# SparkFun_9DoF_Sensor_Stick.net
KiCad netlist of a schematic drawn in EAGLE
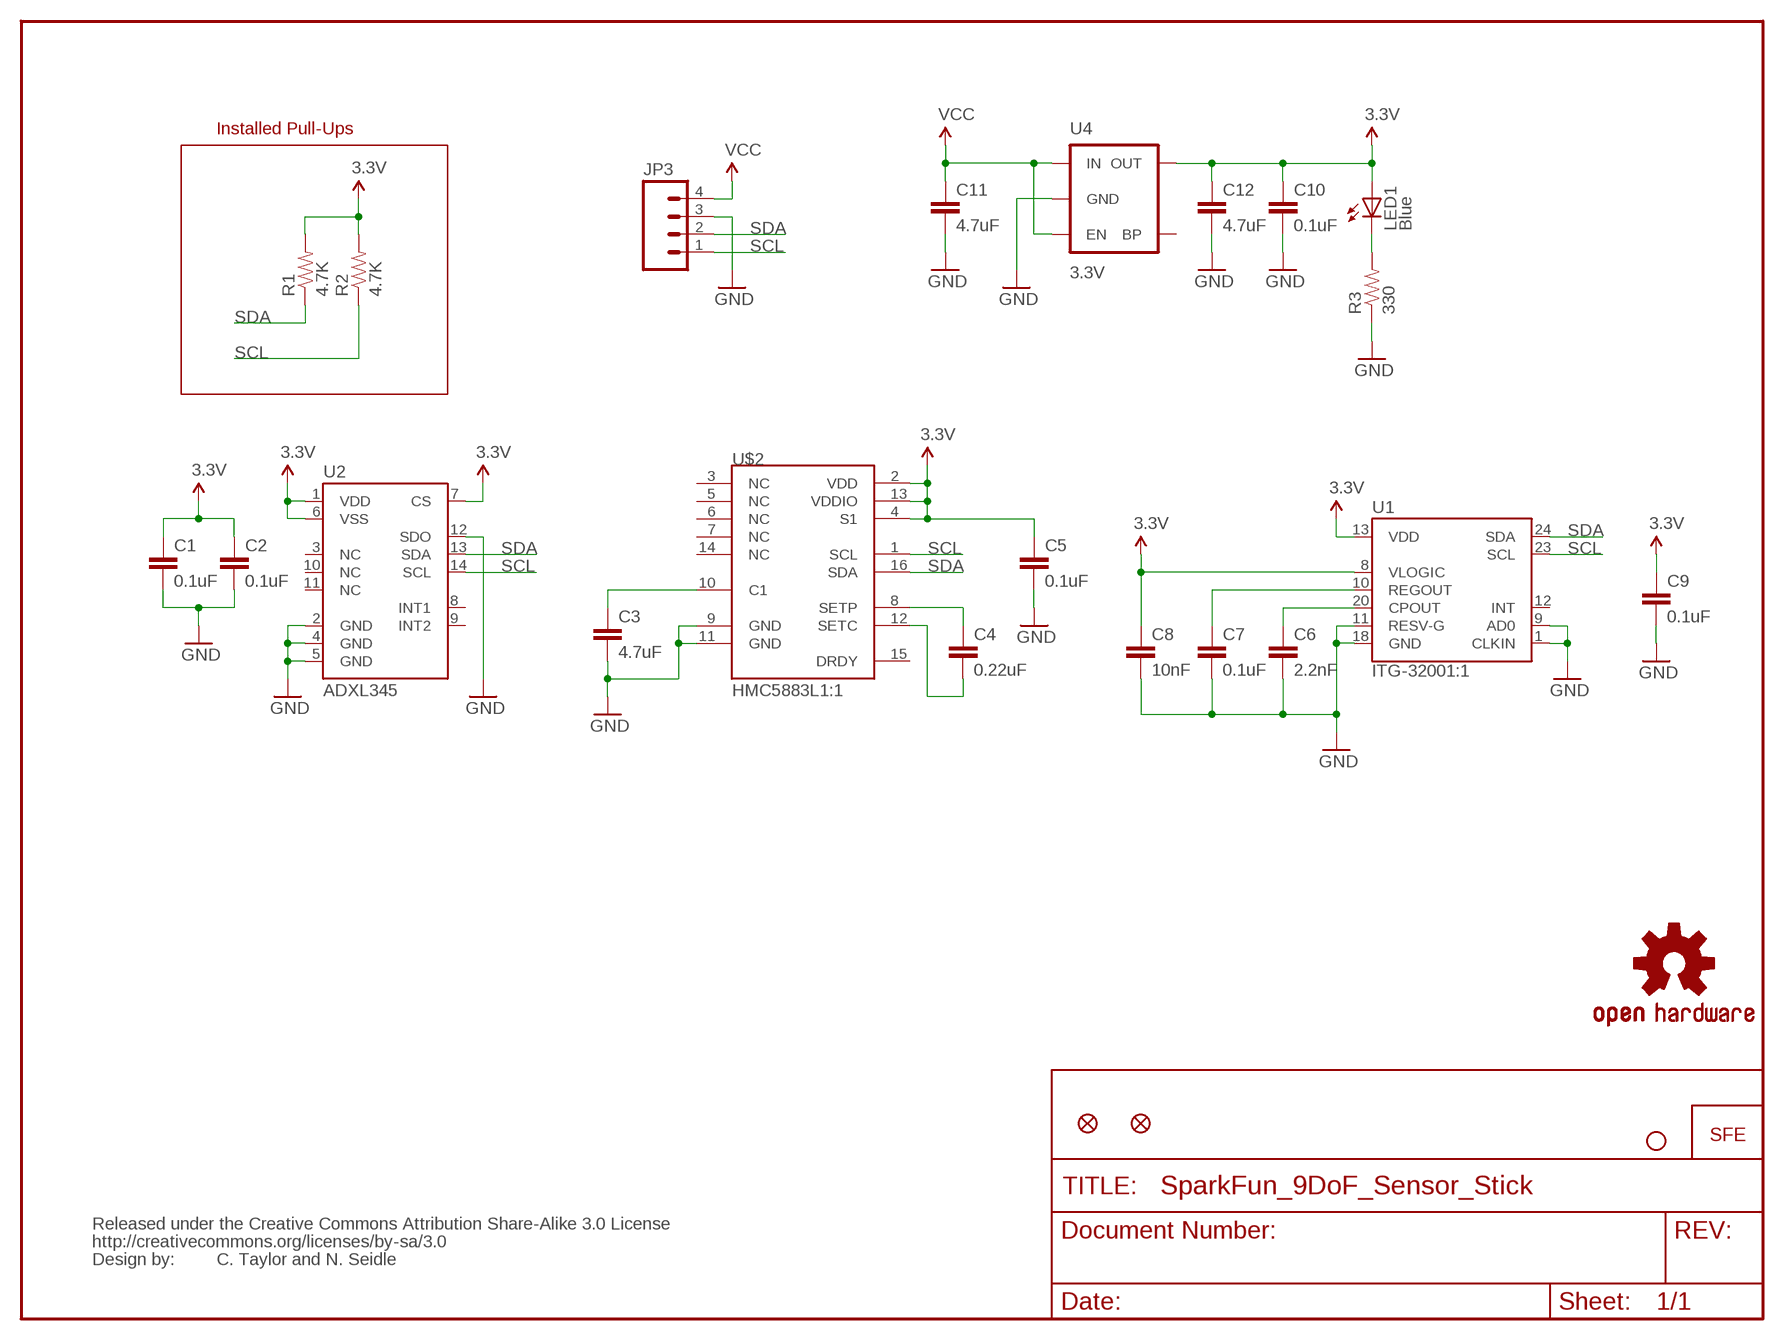
[diagram p0: schematic, sheet 1]

(export (version "E")
  (design (tool "Eeschema 10.0.6"))
  (components
    (comp (ref "C1")
      (value "0.1uF")
      (footprint "eagle-import:0402-CAP")
      (libsource (lib "eagle-import") (part "CAP0402-CAP"))
    )
    (comp (ref "C2")
      (value "0.1uF")
      (footprint "eagle-import:0402-CAP")
      (libsource (lib "eagle-import") (part "CAP0402-CAP"))
    )
    (comp (ref "C3")
      (value "4.7uF")
      (footprint "eagle-import:0402-CAP")
      (libsource (lib "eagle-import") (part "CAP0402-CAP"))
    )
    (comp (ref "C4")
      (value "0.22uF")
      (footprint "eagle-import:0402-CAP")
      (libsource (lib "eagle-import") (part "CAP0402-CAP"))
    )
    (comp (ref "C5")
      (value "0.1uF")
      (footprint "eagle-import:0402-CAP")
      (libsource (lib "eagle-import") (part "CAP0402-CAP"))
    )
    (comp (ref "C6")
      (value "2.2nF")
      (footprint "eagle-import:0402-CAP")
      (libsource (lib "eagle-import") (part "CAP0402-CAP"))
    )
    (comp (ref "C7")
      (value "0.1uF")
      (footprint "eagle-import:0402-CAP")
      (libsource (lib "eagle-import") (part "CAP0402-CAP"))
    )
    (comp (ref "C8")
      (value "10nF")
      (footprint "eagle-import:0402-CAP")
      (libsource (lib "eagle-import") (part "CAP0402-CAP"))
    )
    (comp (ref "C9")
      (value "0.1uF")
      (footprint "eagle-import:0402-CAP")
      (libsource (lib "eagle-import") (part "CAP0402-CAP"))
    )
    (comp (ref "C10")
      (value "0.1uF")
      (footprint "eagle-import:0402-CAP")
      (libsource (lib "eagle-import") (part "CAP0402-CAP"))
    )
    (comp (ref "C11")
      (value "4.7uF")
      (footprint "eagle-import:0402-CAP")
      (libsource (lib "eagle-import") (part "CAP0402-CAP"))
    )
    (comp (ref "C12")
      (value "4.7uF")
      (footprint "eagle-import:0402-CAP")
      (libsource (lib "eagle-import") (part "CAP0402-CAP"))
    )
    (comp (ref "JP1")
      (value "FIDUCIAL1X2")
      (footprint "eagle-import:FIDUCIAL-1X2")
      (libsource (lib "eagle-import") (part "FIDUCIAL1X2"))
    )
    (comp (ref "JP2")
      (value "FIDUCIAL1X2")
      (footprint "eagle-import:FIDUCIAL-1X2")
      (libsource (lib "eagle-import") (part "FIDUCIAL1X2"))
    )
    (comp (ref "JP3")
      (value "M04PTH")
      (footprint "eagle-import:1X04")
      (libsource (lib "eagle-import") (part "M04PTH"))
    )
    (comp (ref "JP4")
      (value "LOGO-SFESK")
      (footprint "eagle-import:SFE-LOGO-FLAME")
      (libsource (lib "eagle-import") (part "LOGO-SFESK"))
    )
    (comp (ref "JP5")
      (value "STAND-OFF")
      (footprint "eagle-import:STAND-OFF")
      (libsource (lib "eagle-import") (part "STAND-OFF"))
    )
    (comp (ref "LED1")
      (value "Blue")
      (footprint "eagle-import:LED-0603")
      (libsource (lib "eagle-import") (part "LED0603"))
    )
    (comp (ref "R1")
      (value "4.7K")
      (footprint "eagle-import:0402-RES")
      (libsource (lib "eagle-import") (part "RESISTOR0402-RES"))
    )
    (comp (ref "R2")
      (value "4.7K")
      (footprint "eagle-import:0402-RES")
      (libsource (lib "eagle-import") (part "RESISTOR0402-RES"))
    )
    (comp (ref "R3")
      (value "330")
      (footprint "eagle-import:0402-RES")
      (libsource (lib "eagle-import") (part "RESISTOR0402-RES"))
    )
    (comp (ref "U$1")
      (value "CREATIVE_COMMONS")
      (footprint "eagle-import:CREATIVE_COMMONS")
      (libsource (lib "eagle-import") (part "CREATIVE_COMMONS"))
    )
    (comp (ref "U$2")
      (value "HMC5883L1:1")
      (footprint "eagle-import:16LPCC_1_1")
      (libsource (lib "eagle-import") (part "HMC5883L1{colon}1"))
    )
    (comp (ref "U$3")
      (value "OSHW-LOGOS")
      (footprint "eagle-import:OSHW-LOGO-S")
      (libsource (lib "eagle-import") (part "OSHW-LOGOS"))
    )
    (comp (ref "U1")
      (value "ITG-32001:1")
      (footprint "eagle-import:QFN-24_1_1")
      (libsource (lib "eagle-import") (part "ITG-32001{colon}1"))
    )
    (comp (ref "U2")
      (value "ADXL345")
      (footprint "eagle-import:LGA14")
      (libsource (lib "eagle-import") (part "ADXL345"))
    )
    (comp (ref "U4")
      (value "3.3V")
      (footprint "eagle-import:SOT23-5")
      (libsource (lib "eagle-import") (part "V_REG_LDOSMD"))
    )
  )
  (nets
    (net (code "1") (name "/SCL") (class "Default")
      (node (ref "JP3") (pin "1") (pinfunction "1_1") (pintype "passive"))
      (node (ref "R2") (pin "1") (pinfunction "1_1") (pintype "passive"))
      (node (ref "U$2") (pin "1") (pinfunction "SCL_1") (pintype "bidirectional"))
      (node (ref "U1") (pin "23") (pinfunction "SCL_23") (pintype "bidirectional"))
      (node (ref "U2") (pin "14") (pinfunction "SCL_14") (pintype "bidirectional"))
    )
    (net (code "2") (name "/SDA") (class "Default")
      (node (ref "JP3") (pin "2") (pinfunction "2_2") (pintype "passive"))
      (node (ref "R1") (pin "1") (pinfunction "1_1") (pintype "passive"))
      (node (ref "U$2") (pin "16") (pinfunction "SDA_16") (pintype "bidirectional"))
      (node (ref "U1") (pin "24") (pinfunction "SDA_24") (pintype "bidirectional"))
      (node (ref "U2") (pin "13") (pinfunction "SDA_13") (pintype "bidirectional"))
    )
    (net (code "3") (name "3.3V") (class "Default")
      (node (ref "C1") (pin "1") (pinfunction "1_1") (pintype "passive"))
      (node (ref "C10") (pin "1") (pinfunction "1_1") (pintype "passive"))
      (node (ref "C12") (pin "1") (pinfunction "1_1") (pintype "passive"))
      (node (ref "C2") (pin "1") (pinfunction "1_1") (pintype "passive"))
      (node (ref "C5") (pin "1") (pinfunction "1_1") (pintype "passive"))
      (node (ref "C8") (pin "1") (pinfunction "1_1") (pintype "passive"))
      (node (ref "C9") (pin "1") (pinfunction "1_1") (pintype "passive"))
      (node (ref "LED1") (pin "A") (pinfunction "A_A") (pintype "passive"))
      (node (ref "R1") (pin "2") (pinfunction "2_2") (pintype "passive"))
      (node (ref "R2") (pin "2") (pinfunction "2_2") (pintype "passive"))
      (node (ref "U$2") (pin "13") (pinfunction "VDDIO_13") (pintype "bidirectional"))
      (node (ref "U$2") (pin "2") (pinfunction "VDD_2") (pintype "bidirectional"))
      (node (ref "U$2") (pin "4") (pinfunction "S1_4") (pintype "bidirectional"))
      (node (ref "U1") (pin "13") (pinfunction "VDD_13") (pintype "bidirectional"))
      (node (ref "U1") (pin "8") (pinfunction "VLOGIC_8") (pintype "bidirectional"))
      (node (ref "U2") (pin "1") (pinfunction "VDD_1") (pintype "bidirectional"))
      (node (ref "U2") (pin "6") (pinfunction "VSS_6") (pintype "bidirectional"))
      (node (ref "U2") (pin "7") (pinfunction "CS_7") (pintype "bidirectional"))
      (node (ref "U4") (pin "5") (pinfunction "OUT_5") (pintype "passive"))
    )
    (net (code "4") (name "GND") (class "Default")
      (node (ref "C1") (pin "2") (pinfunction "2_2") (pintype "passive"))
      (node (ref "C10") (pin "2") (pinfunction "2_2") (pintype "passive"))
      (node (ref "C11") (pin "2") (pinfunction "2_2") (pintype "passive"))
      (node (ref "C12") (pin "2") (pinfunction "2_2") (pintype "passive"))
      (node (ref "C2") (pin "2") (pinfunction "2_2") (pintype "passive"))
      (node (ref "C3") (pin "2") (pinfunction "2_2") (pintype "passive"))
      (node (ref "C5") (pin "2") (pinfunction "2_2") (pintype "passive"))
      (node (ref "C6") (pin "2") (pinfunction "2_2") (pintype "passive"))
      (node (ref "C7") (pin "2") (pinfunction "2_2") (pintype "passive"))
      (node (ref "C8") (pin "2") (pinfunction "2_2") (pintype "passive"))
      (node (ref "C9") (pin "2") (pinfunction "2_2") (pintype "passive"))
      (node (ref "JP3") (pin "3") (pinfunction "3_3") (pintype "passive"))
      (node (ref "R3") (pin "1") (pinfunction "1_1") (pintype "passive"))
      (node (ref "U$2") (pin "11") (pinfunction "GND_11") (pintype "bidirectional"))
      (node (ref "U$2") (pin "9") (pinfunction "GND_9") (pintype "bidirectional"))
      (node (ref "U1") (pin "1") (pinfunction "CLKIN_1") (pintype "bidirectional"))
      (node (ref "U1") (pin "11") (pinfunction "RESV-G_11") (pintype "bidirectional"))
      (node (ref "U1") (pin "18") (pinfunction "GND_18") (pintype "bidirectional"))
      (node (ref "U1") (pin "9") (pinfunction "AD0_9") (pintype "bidirectional"))
      (node (ref "U2") (pin "12") (pinfunction "SDO_12") (pintype "bidirectional"))
      (node (ref "U2") (pin "2") (pinfunction "GND_2") (pintype "bidirectional"))
      (node (ref "U2") (pin "4") (pinfunction "GND_4") (pintype "bidirectional"))
      (node (ref "U2") (pin "5") (pinfunction "GND_5") (pintype "bidirectional"))
      (node (ref "U4") (pin "2") (pinfunction "GND_2") (pintype "input"))
    )
    (net (code "5") (name "Net-(LED1-PadC)") (class "Default")
      (node (ref "LED1") (pin "C") (pinfunction "C_C") (pintype "passive"))
      (node (ref "R3") (pin "2") (pinfunction "2_2") (pintype "passive"))
    )
    (net (code "6") (name "Net-(U$2-C1)") (class "Default")
      (node (ref "C3") (pin "1") (pinfunction "1_1") (pintype "passive"))
      (node (ref "U$2") (pin "10") (pinfunction "C1_10") (pintype "bidirectional"))
    )
    (net (code "7") (name "Net-(U$2-SETC)") (class "Default")
      (node (ref "C4") (pin "2") (pinfunction "2_2") (pintype "passive"))
      (node (ref "U$2") (pin "12") (pinfunction "SETC_12") (pintype "bidirectional"))
    )
    (net (code "8") (name "Net-(U$2-SETP)") (class "Default")
      (node (ref "C4") (pin "1") (pinfunction "1_1") (pintype "passive"))
      (node (ref "U$2") (pin "8") (pinfunction "SETP_8") (pintype "bidirectional"))
    )
    (net (code "9") (name "Net-(U1-CPOUT)") (class "Default")
      (node (ref "C6") (pin "1") (pinfunction "1_1") (pintype "passive"))
      (node (ref "U1") (pin "20") (pinfunction "CPOUT_20") (pintype "bidirectional"))
    )
    (net (code "10") (name "Net-(U1-REGOUT)") (class "Default")
      (node (ref "C7") (pin "1") (pinfunction "1_1") (pintype "passive"))
      (node (ref "U1") (pin "10") (pinfunction "REGOUT_10") (pintype "bidirectional"))
    )
    (net (code "11") (name "VCC") (class "Default")
      (node (ref "C11") (pin "1") (pinfunction "1_1") (pintype "passive"))
      (node (ref "JP3") (pin "4") (pinfunction "4_4") (pintype "passive"))
      (node (ref "U4") (pin "1") (pinfunction "IN_1") (pintype "input"))
      (node (ref "U4") (pin "3") (pinfunction "EN_3") (pintype "input"))
    )
    (net (code "12") (name "unconnected-(U$2-DRDY-Pad15)") (class "Default")
      (node (ref "U$2") (pin "15") (pinfunction "DRDY_15") (pintype "bidirectional"))
    )
    (net (code "13") (name "unconnected-(U$2-NC-Pad3)") (class "Default")
      (node (ref "U$2") (pin "3") (pinfunction "NC_3") (pintype "bidirectional"))
    )
    (net (code "14") (name "unconnected-(U$2-NC-Pad5)") (class "Default")
      (node (ref "U$2") (pin "5") (pinfunction "NC_5") (pintype "bidirectional"))
    )
    (net (code "15") (name "unconnected-(U$2-NC-Pad6)") (class "Default")
      (node (ref "U$2") (pin "6") (pinfunction "NC_6") (pintype "bidirectional"))
    )
    (net (code "16") (name "unconnected-(U$2-NC-Pad7)") (class "Default")
      (node (ref "U$2") (pin "7") (pinfunction "NC_7") (pintype "bidirectional"))
    )
    (net (code "17") (name "unconnected-(U$2-NC-Pad14)") (class "Default")
      (node (ref "U$2") (pin "14") (pinfunction "NC_14") (pintype "bidirectional"))
    )
    (net (code "18") (name "unconnected-(U1-INT-Pad12)") (class "Default")
      (node (ref "U1") (pin "12") (pinfunction "INT_12") (pintype "bidirectional"))
    )
    (net (code "19") (name "unconnected-(U2-INT1-Pad8)") (class "Default")
      (node (ref "U2") (pin "8") (pinfunction "INT1_8") (pintype "bidirectional"))
    )
    (net (code "20") (name "unconnected-(U2-INT2-Pad9)") (class "Default")
      (node (ref "U2") (pin "9") (pinfunction "INT2_9") (pintype "bidirectional"))
    )
    (net (code "21") (name "unconnected-(U2-NC-Pad3)") (class "Default")
      (node (ref "U2") (pin "3") (pinfunction "NC_3") (pintype "bidirectional"))
    )
    (net (code "22") (name "unconnected-(U2-NC-Pad10)") (class "Default")
      (node (ref "U2") (pin "10") (pinfunction "NC_10") (pintype "bidirectional"))
    )
    (net (code "23") (name "unconnected-(U2-NC-Pad11)") (class "Default")
      (node (ref "U2") (pin "11") (pinfunction "NC_11") (pintype "bidirectional"))
    )
    (net (code "24") (name "unconnected-(U4-BP-Pad4)") (class "Default")
      (node (ref "U4") (pin "4") (pinfunction "BP_4") (pintype "input"))
    )
  )
)
